# Sheet4_MCU_Sensors.net
KiCad netlist of a schematic drawn in Altium Designer
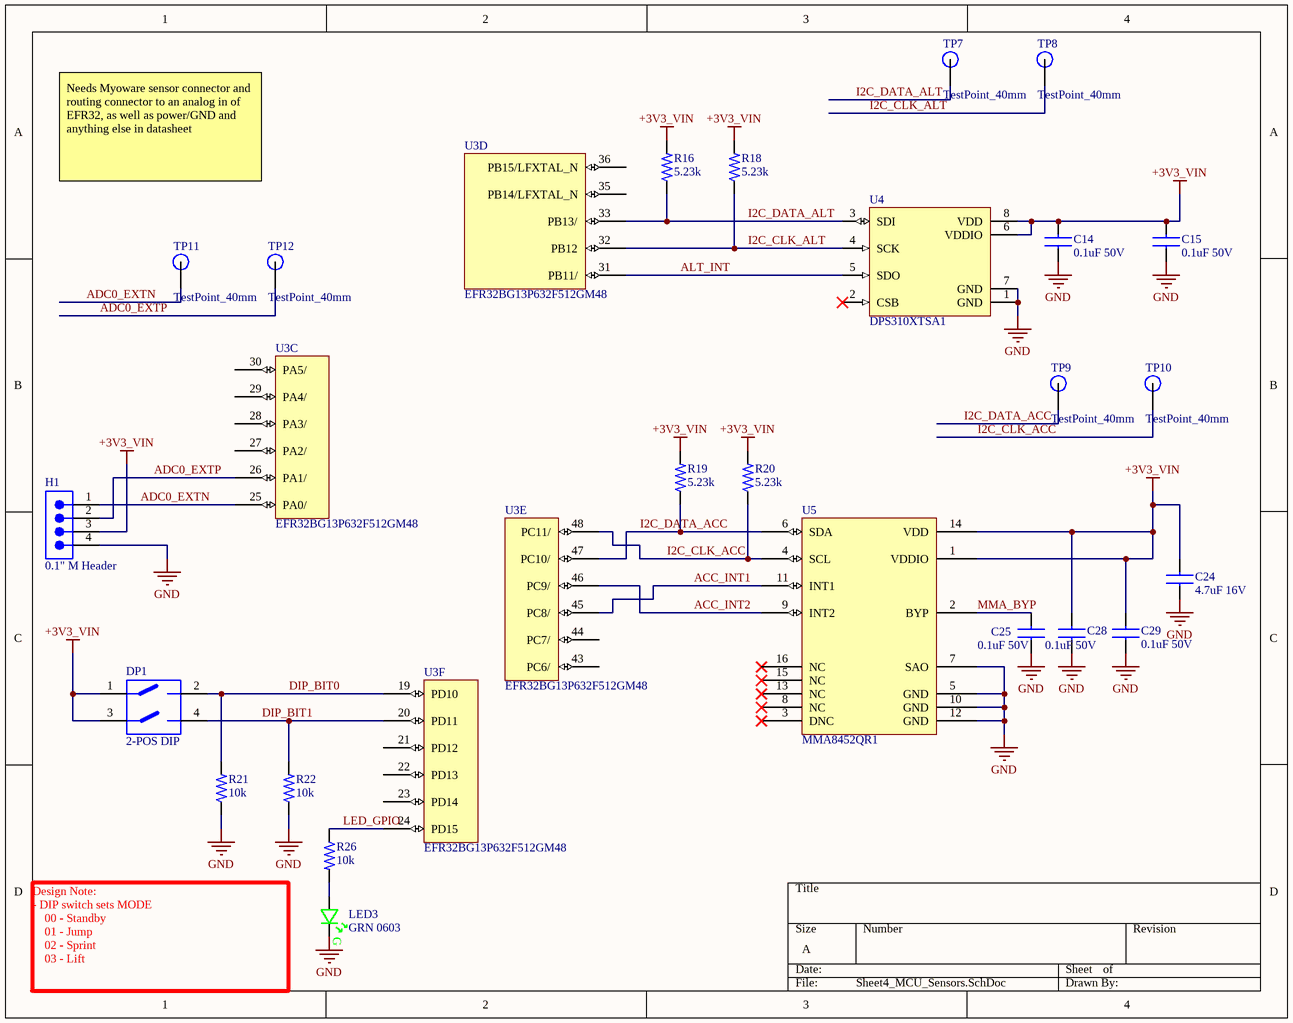
[diagram p0: Sheet4_MCU_Sensors.SchDoc]

(export (version "E")
  (design (tool "Eeschema 10.0.6"))
  (components
    (comp (ref "C14")
      (value "0.1uF 50V")
      (footprint "CAP_0603_1MM")
      (description "CAPACITOR CERAMIC, 0.1UF, 50V, X7R, 10%, 0603")
      (fields
        (field (name "MANUFACTURER") "Yageo")
        (field (name "MANUFACTURER PART NUMBER") "CC0603KRX7R9BB104")
      )
      (libsource (lib "LPEDT_Parts") (part "CC0603KRX7R9BB104"))
    )
    (comp (ref "C15")
      (value "0.1uF 50V")
      (footprint "CAP_0603_1MM")
      (description "CAPACITOR CERAMIC, 0.1UF, 50V, X7R, 10%, 0603")
      (fields
        (field (name "MANUFACTURER") "Yageo")
        (field (name "MANUFACTURER PART NUMBER") "CC0603KRX7R9BB104")
      )
      (libsource (lib "LPEDT_Parts") (part "CC0603KRX7R9BB104"))
    )
    (comp (ref "C24")
      (value "4.7uF 16V")
      (footprint "CAP_0805_1_4MM")
      (description "CAP CER 4.7UF 16V X5R 0805")
      (fields
        (field (name "MANUFACTURER") "Samsung")
        (field (name "MANUFACTURER PART NUMBER") "CL21A475KOFNNNG")
      )
      (libsource (lib "LPEDT_Parts") (part "CL21A475KOFNNNG"))
    )
    (comp (ref "C25")
      (value "0.1uF 50V")
      (footprint "CAP_0603_1MM")
      (description "CAPACITOR CERAMIC, 0.1UF, 50V, X7R, 10%, 0603")
      (fields
        (field (name "MANUFACTURER") "Yageo")
        (field (name "MANUFACTURER PART NUMBER") "CC0603KRX7R9BB104")
      )
      (libsource (lib "LPEDT_Parts") (part "CC0603KRX7R9BB104"))
    )
    (comp (ref "C28")
      (value "0.1uF 50V")
      (footprint "CAP_0603_1MM")
      (description "CAPACITOR CERAMIC, 0.1UF, 50V, X7R, 10%, 0603")
      (fields
        (field (name "MANUFACTURER") "Yageo")
        (field (name "MANUFACTURER PART NUMBER") "CC0603KRX7R9BB104")
      )
      (libsource (lib "LPEDT_Parts") (part "CC0603KRX7R9BB104"))
    )
    (comp (ref "C29")
      (value "0.1uF 50V")
      (footprint "CAP_0603_1MM")
      (description "CAPACITOR CERAMIC, 0.1UF, 50V, X7R, 10%, 0603")
      (fields
        (field (name "MANUFACTURER") "Yageo")
        (field (name "MANUFACTURER PART NUMBER") "CC0603KRX7R9BB104")
      )
      (libsource (lib "LPEDT_Parts") (part "CC0603KRX7R9BB104"))
    )
    (comp (ref "DP1")
      (value "2-POS DIP")
      (footprint "4-PIN_DIP_2.54MM")
      (description "SWITCH SLIDE DIP SPST 50MA 24V")
      (libsource (lib "LPEDT_Parts") (part "206-2"))
    )
    (comp (ref "H1")
      (value "0.1\" M Header")
      (footprint "4-PIN_MALE_HEADER_01-IN")
      (description "CONN HEADER VERT 4POS 2.54MM")
      (fields
        (field (name "MANUFACTURER") "Sullins")
        (field (name "MANUFACTURER PART NUMBER") "PRPC004SAAN-RC")
      )
      (libsource (lib "LPEDT_Parts") (part "PRPC004SAAN-RC"))
    )
    (comp (ref "LED3")
      (value "GRN 0603")
      (footprint "LED_0603_GRN_WL-SMCW")
      (description "LED, 0603, GREEN, 430MCD, 520NM")
      (fields
        (field (name "MANUFACTURER") "Wurth Electronics")
        (field (name "MANUFACTURER PART NUMBER") "150060GS75000")
      )
      (libsource (lib "LPEDT_Parts") (part "150060GS75000"))
    )
    (comp (ref "R16")
      (value "5.23k")
      (footprint "RES_0603_1608X06")
      (description "RES SMD 5.23K OHM 1% 1/10W 0603")
      (fields
        (field (name "MANUFACTURER") "Stackpole Electronics")
        (field (name "MANUFACTURER PART NUMBER") "RMCF0603FT5K23")
      )
      (libsource (lib "LPEDT_Parts") (part "RMCF0603FT5K23"))
    )
    (comp (ref "R18")
      (value "5.23k")
      (footprint "RES_0603_1608X06")
      (description "RES SMD 5.23K OHM 1% 1/10W 0603")
      (fields
        (field (name "MANUFACTURER") "Stackpole Electronics")
        (field (name "MANUFACTURER PART NUMBER") "RMCF0603FT5K23")
      )
      (libsource (lib "LPEDT_Parts") (part "RMCF0603FT5K23"))
    )
    (comp (ref "R19")
      (value "5.23k")
      (footprint "RES_0603_1608X06")
      (description "RES SMD 5.23K OHM 1% 1/10W 0603")
      (fields
        (field (name "MANUFACTURER") "Stackpole Electronics")
        (field (name "MANUFACTURER PART NUMBER") "RMCF0603FT5K23")
      )
      (libsource (lib "LPEDT_Parts") (part "RMCF0603FT5K23"))
    )
    (comp (ref "R20")
      (value "5.23k")
      (footprint "RES_0603_1608X06")
      (description "RES SMD 5.23K OHM 1% 1/10W 0603")
      (fields
        (field (name "MANUFACTURER") "Stackpole Electronics")
        (field (name "MANUFACTURER PART NUMBER") "RMCF0603FT5K23")
      )
      (libsource (lib "LPEDT_Parts") (part "RMCF0603FT5K23"))
    )
    (comp (ref "R21")
      (value "10k")
      (footprint "RES_0805_2X1_25MM")
      (description "RES 10K OHM 1% 1/8W 0805")
      (fields
        (field (name "MANUFACTURER") "Stackpole Electronics")
        (field (name "MANUFACTURER PART NUMBER") "RMCF0805FT10K0")
      )
      (libsource (lib "LPEDT_Parts") (part "RMCF0805FT10K0"))
    )
    (comp (ref "R22")
      (value "10k")
      (footprint "RES_0805_2X1_25MM")
      (description "RES 10K OHM 1% 1/8W 0805")
      (fields
        (field (name "MANUFACTURER") "Stackpole Electronics")
        (field (name "MANUFACTURER PART NUMBER") "RMCF0805FT10K0")
      )
      (libsource (lib "LPEDT_Parts") (part "RMCF0805FT10K0"))
    )
    (comp (ref "R26")
      (value "10k")
      (footprint "RES_0805_2X1_25MM")
      (description "RES 10K OHM 1% 1/8W 0805")
      (fields
        (field (name "MANUFACTURER") "Stackpole Electronics")
        (field (name "MANUFACTURER PART NUMBER") "RMCF0805FT10K0")
      )
      (libsource (lib "LPEDT_Parts") (part "RMCF0805FT10K0"))
    )
    (comp (ref "TP7")
      (value "TestPoint_40mm")
      (footprint "TP_40MM")
      (libsource (lib "LPEDT_Parts") (part "TestPoint_40mm"))
    )
    (comp (ref "TP8")
      (value "TestPoint_40mm")
      (footprint "TP_40MM")
      (libsource (lib "LPEDT_Parts") (part "TestPoint_40mm"))
    )
    (comp (ref "TP9")
      (value "TestPoint_40mm")
      (footprint "TP_40MM")
      (libsource (lib "LPEDT_Parts") (part "TestPoint_40mm"))
    )
    (comp (ref "TP10")
      (value "TestPoint_40mm")
      (footprint "TP_40MM")
      (libsource (lib "LPEDT_Parts") (part "TestPoint_40mm"))
    )
    (comp (ref "TP11")
      (value "TestPoint_40mm")
      (footprint "TP_40MM")
      (libsource (lib "LPEDT_Parts") (part "TestPoint_40mm"))
    )
    (comp (ref "TP12")
      (value "TestPoint_40mm")
      (footprint "TP_40MM")
      (libsource (lib "LPEDT_Parts") (part "TestPoint_40mm"))
    )
    (comp (ref "U3")
      (value "EFR32BG13P632F512GM48")
      (footprint "QFN50P700X700X90_HS-49N")
      (description "BLUE PREMIUM QFN48 2.4G 19 DBM B")
      (fields
        (field (name "MANUFACTURER") "Silicon Labs")
        (field (name "MANUFACTURER PART NUMBER") "EFR32BG13P732F512GM48-B")
      )
      (libsource (lib "") (part "EFR32BG13P732F512GM48-B_1_2"))
    )
    (comp (ref "U4")
      (value "DPS310XTSA1")
      (footprint "8-VLGA_2x2_5x1")
      (description "INFINEON - DPS310XTSA1 - Pressure Sensor, Barometric, 17.404 psi, 4.351 psi, 1.7 V, 3.6 V")
      (fields (field (name "MANUFACTURER") "Infineon"))
      (libsource (lib "LPEDT_Parts") (part "DPS310XTSA1"))
    )
    (comp (ref "U5")
      (value "MMA8452QR1")
      (footprint "MMA8452")
      (description "Accelerometer Triple ±2g/±4g/±8g 2.5V 16-Pin QFN T/R")
      (fields (field (name "MANUFACTURER") "NXP Freescale"))
      (libsource (lib "LPEDT_Parts") (part "MMA8452QR1"))
    )
  )
  (nets
    (net (code "1") (name "+3V3_VIN") (class "Default")
      (node (ref "C14") (pin "1") (pinfunction "1_1") (pintype "passive"))
      (node (ref "C15") (pin "1") (pinfunction "1_1") (pintype "passive"))
      (node (ref "C24") (pin "2") (pinfunction "2_2") (pintype "passive"))
      (node (ref "C28") (pin "1") (pinfunction "1_1") (pintype "passive"))
      (node (ref "C29") (pin "1") (pinfunction "1_1") (pintype "passive"))
      (node (ref "DP1") (pin "1") (pinfunction "1_1") (pintype "passive"))
      (node (ref "DP1") (pin "3") (pinfunction "3_3") (pintype "passive"))
      (node (ref "H1") (pin "3") (pinfunction "3_3") (pintype "passive"))
      (node (ref "R16") (pin "2") (pinfunction "2_2") (pintype "passive"))
      (node (ref "R18") (pin "2") (pinfunction "2_2") (pintype "passive"))
      (node (ref "R19") (pin "2") (pinfunction "2_2") (pintype "passive"))
      (node (ref "R20") (pin "2") (pinfunction "2_2") (pintype "passive"))
      (node (ref "U4") (pin "6") (pinfunction "VDDIO_6") (pintype "power_in"))
      (node (ref "U4") (pin "8") (pinfunction "VDD_8") (pintype "power_in"))
      (node (ref "U5") (pin "1") (pinfunction "VDDIO_1") (pintype "power_in"))
      (node (ref "U5") (pin "14") (pinfunction "VDD_14") (pintype "power_in"))
    )
    (net (code "2") (name "/ACC_INT1") (class "Default")
      (node (ref "U3") (pin "45") (pinfunction "PC8/_45") (pintype "bidirectional"))
      (node (ref "U5") (pin "11") (pinfunction "INT1_11") (pintype "bidirectional"))
    )
    (net (code "3") (name "/ACC_INT2") (class "Default")
      (node (ref "U3") (pin "46") (pinfunction "PC9/_46") (pintype "bidirectional"))
      (node (ref "U5") (pin "9") (pinfunction "INT2_9") (pintype "bidirectional"))
    )
    (net (code "4") (name "/ADC0_EXTN") (class "Default")
      (node (ref "H1") (pin "1") (pinfunction "1_1") (pintype "passive"))
      (node (ref "TP11") (pin "1") (pinfunction "1_1") (pintype "passive"))
      (node (ref "U3") (pin "25") (pinfunction "PA0/_25") (pintype "bidirectional"))
    )
    (net (code "5") (name "/ADC0_EXTP") (class "Default")
      (node (ref "H1") (pin "2") (pinfunction "2_2") (pintype "passive"))
      (node (ref "TP12") (pin "1") (pinfunction "1_1") (pintype "passive"))
      (node (ref "U3") (pin "26") (pinfunction "PA1/_26") (pintype "bidirectional"))
    )
    (net (code "6") (name "/ALT_INT") (class "Default")
      (node (ref "U3") (pin "31") (pinfunction "PB11/_31") (pintype "bidirectional"))
      (node (ref "U4") (pin "5") (pinfunction "SDO_5") (pintype "input"))
    )
    (net (code "7") (name "/DIP_BIT0") (class "Default")
      (node (ref "DP1") (pin "2") (pinfunction "2_2") (pintype "passive"))
      (node (ref "R21") (pin "2") (pinfunction "2_2") (pintype "passive"))
      (node (ref "U3") (pin "19") (pinfunction "PD10_19") (pintype "bidirectional"))
    )
    (net (code "8") (name "/DIP_BIT1") (class "Default")
      (node (ref "DP1") (pin "4") (pinfunction "4_4") (pintype "passive"))
      (node (ref "R22") (pin "2") (pinfunction "2_2") (pintype "passive"))
      (node (ref "U3") (pin "20") (pinfunction "PD11_20") (pintype "bidirectional"))
    )
    (net (code "9") (name "/I2C_CLK_ACC") (class "Default")
      (node (ref "R20") (pin "1") (pinfunction "1_1") (pintype "passive"))
      (node (ref "TP10") (pin "1") (pinfunction "1_1") (pintype "passive"))
      (node (ref "U3") (pin "48") (pinfunction "PC11/_48") (pintype "bidirectional"))
      (node (ref "U5") (pin "4") (pinfunction "SCL_4") (pintype "bidirectional"))
    )
    (net (code "10") (name "/I2C_CLK_ALT") (class "Default")
      (node (ref "R18") (pin "1") (pinfunction "1_1") (pintype "passive"))
      (node (ref "TP8") (pin "1") (pinfunction "1_1") (pintype "passive"))
      (node (ref "U3") (pin "32") (pinfunction "PB12_32") (pintype "bidirectional"))
      (node (ref "U4") (pin "4") (pinfunction "SCK_4") (pintype "input"))
    )
    (net (code "11") (name "/I2C_DATA_ACC") (class "Default")
      (node (ref "R19") (pin "1") (pinfunction "1_1") (pintype "passive"))
      (node (ref "TP9") (pin "1") (pinfunction "1_1") (pintype "passive"))
      (node (ref "U3") (pin "47") (pinfunction "PC10/_47") (pintype "bidirectional"))
      (node (ref "U5") (pin "6") (pinfunction "SDA_6") (pintype "bidirectional"))
    )
    (net (code "12") (name "/I2C_DATA_ALT") (class "Default")
      (node (ref "R16") (pin "1") (pinfunction "1_1") (pintype "passive"))
      (node (ref "TP7") (pin "1") (pinfunction "1_1") (pintype "passive"))
      (node (ref "U3") (pin "33") (pinfunction "PB13/_33") (pintype "bidirectional"))
      (node (ref "U4") (pin "3") (pinfunction "SDI_3") (pintype "bidirectional"))
    )
    (net (code "13") (name "/LED_GPIO") (class "Default")
      (node (ref "R26") (pin "1") (pinfunction "1_1") (pintype "passive"))
      (node (ref "U3") (pin "24") (pinfunction "PD15_24") (pintype "bidirectional"))
    )
    (net (code "14") (name "/MMA_BYP") (class "Default")
      (node (ref "C25") (pin "1") (pinfunction "1_1") (pintype "passive"))
      (node (ref "U5") (pin "2") (pinfunction "BYP_2") (pintype "passive"))
    )
    (net (code "15") (name "GND") (class "Default")
      (node (ref "C14") (pin "2") (pinfunction "2_2") (pintype "passive"))
      (node (ref "C15") (pin "2") (pinfunction "2_2") (pintype "passive"))
      (node (ref "C24") (pin "1") (pinfunction "1_1") (pintype "passive"))
      (node (ref "C25") (pin "2") (pinfunction "2_2") (pintype "passive"))
      (node (ref "C28") (pin "2") (pinfunction "2_2") (pintype "passive"))
      (node (ref "C29") (pin "2") (pinfunction "2_2") (pintype "passive"))
      (node (ref "H1") (pin "4") (pinfunction "4_4") (pintype "passive"))
      (node (ref "LED3") (pin "C") (pinfunction "C_C") (pintype "passive"))
      (node (ref "R21") (pin "1") (pinfunction "1_1") (pintype "passive"))
      (node (ref "R22") (pin "1") (pinfunction "1_1") (pintype "passive"))
      (node (ref "U4") (pin "1") (pinfunction "GND_1") (pintype "power_in"))
      (node (ref "U4") (pin "7") (pinfunction "GND_7") (pintype "power_in"))
      (node (ref "U5") (pin "10") (pinfunction "GND_10") (pintype "power_in"))
      (node (ref "U5") (pin "12") (pinfunction "GND_12") (pintype "power_in"))
      (node (ref "U5") (pin "5") (pinfunction "GND_5") (pintype "power_in"))
      (node (ref "U5") (pin "7") (pinfunction "SAO_7") (pintype "passive"))
    )
    (net (code "16") (name "Net-(LED3-PadA)") (class "Default")
      (node (ref "LED3") (pin "A") (pinfunction "A_A") (pintype "passive"))
      (node (ref "R26") (pin "2") (pinfunction "2_2") (pintype "passive"))
    )
    (net (code "17") (name "unconnected-(U3C-PA2{slash}-Pad27)") (class "Default")
      (node (ref "U3") (pin "27") (pinfunction "PA2/_27") (pintype "bidirectional"))
    )
    (net (code "18") (name "unconnected-(U3C-PA3{slash}-Pad28)") (class "Default")
      (node (ref "U3") (pin "28") (pinfunction "PA3/_28") (pintype "bidirectional"))
    )
    (net (code "19") (name "unconnected-(U3C-PA4{slash}-Pad29)") (class "Default")
      (node (ref "U3") (pin "29") (pinfunction "PA4/_29") (pintype "bidirectional"))
    )
    (net (code "20") (name "unconnected-(U3C-PA5{slash}-Pad30)") (class "Default")
      (node (ref "U3") (pin "30") (pinfunction "PA5/_30") (pintype "bidirectional"))
    )
    (net (code "21") (name "unconnected-(U3D-PB14{slash}LFXTAL_N-Pad35)") (class "Default")
      (node (ref "U3") (pin "35") (pinfunction "PB14/LFXTAL_N_35") (pintype "bidirectional"))
    )
    (net (code "22") (name "unconnected-(U3D-PB15{slash}LFXTAL_N-Pad36)") (class "Default")
      (node (ref "U3") (pin "36") (pinfunction "PB15/LFXTAL_N_36") (pintype "bidirectional"))
    )
    (net (code "23") (name "unconnected-(U3E-PC6{slash}-Pad43)") (class "Default")
      (node (ref "U3") (pin "43") (pinfunction "PC6/_43") (pintype "bidirectional"))
    )
    (net (code "24") (name "unconnected-(U3E-PC7{slash}-Pad44)") (class "Default")
      (node (ref "U3") (pin "44") (pinfunction "PC7/_44") (pintype "bidirectional"))
    )
    (net (code "25") (name "unconnected-(U3F-PD12-Pad21)") (class "Default")
      (node (ref "U3") (pin "21") (pinfunction "PD12_21") (pintype "bidirectional"))
    )
    (net (code "26") (name "unconnected-(U3F-PD13-Pad22)") (class "Default")
      (node (ref "U3") (pin "22") (pinfunction "PD13_22") (pintype "bidirectional"))
    )
    (net (code "27") (name "unconnected-(U3F-PD14-Pad23)") (class "Default")
      (node (ref "U3") (pin "23") (pinfunction "PD14_23") (pintype "bidirectional"))
    )
    (net (code "28") (name "unconnected-(U4-CSB-Pad2)") (class "Default")
      (node (ref "U4") (pin "2") (pinfunction "CSB_2") (pintype "input+no_connect"))
    )
    (net (code "29") (name "unconnected-(U5-DNC-Pad3)") (class "Default")
      (node (ref "U5") (pin "3") (pinfunction "DNC_3") (pintype "passive+no_connect"))
    )
    (net (code "30") (name "unconnected-(U5-NC-Pad8)") (class "Default")
      (node (ref "U5") (pin "8") (pinfunction "NC_8") (pintype "passive+no_connect"))
    )
    (net (code "31") (name "unconnected-(U5-NC-Pad13)") (class "Default")
      (node (ref "U5") (pin "13") (pinfunction "NC_13") (pintype "passive+no_connect"))
    )
    (net (code "32") (name "unconnected-(U5-NC-Pad15)") (class "Default")
      (node (ref "U5") (pin "15") (pinfunction "NC_15") (pintype "passive+no_connect"))
    )
    (net (code "33") (name "unconnected-(U5-NC-Pad16)") (class "Default")
      (node (ref "U5") (pin "16") (pinfunction "NC_16") (pintype "passive+no_connect"))
    )
  )
)
